# Grove_-_Collision_Sensor_v2_0.net
KiCad netlist of a schematic drawn in EAGLE
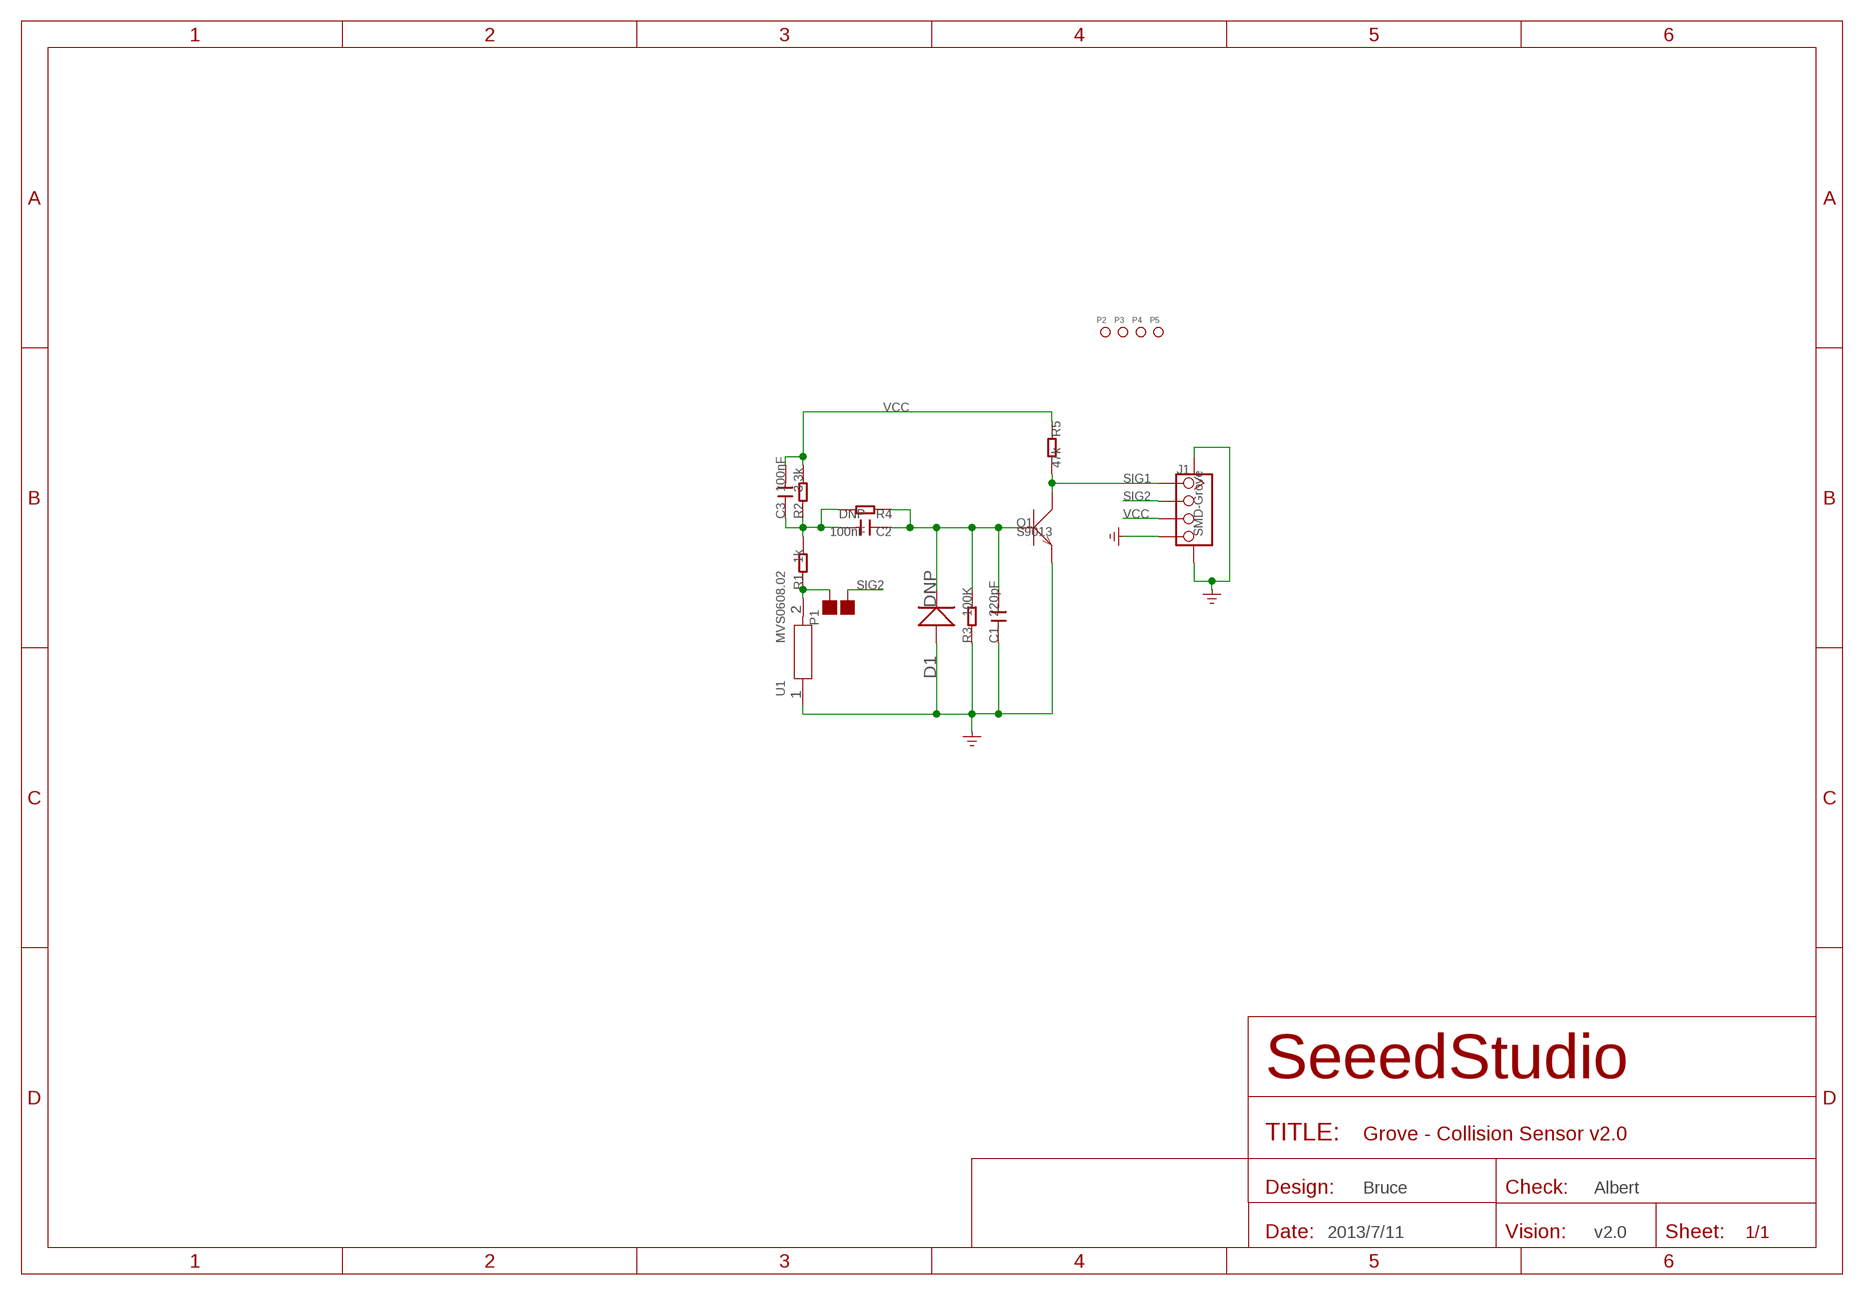
[diagram p0: schematic, sheet 1]

(export (version "E")
  (design (tool "Eeschema 10.0.6"))
  (components
    (comp (ref "C1")
      (value "220pF")
      (footprint "eagle-import:C0603")
      (libsource (lib "eagle-import") (part "C-0603"))
    )
    (comp (ref "C2")
      (value "100nF")
      (footprint "eagle-import:C0603")
      (libsource (lib "eagle-import") (part "C-0603"))
    )
    (comp (ref "C3")
      (value "100nF")
      (footprint "eagle-import:C0603")
      (libsource (lib "eagle-import") (part "C-0603"))
    )
    (comp (ref "D1")
      (value "DNP")
      (footprint "eagle-import:SOD123")
      (libsource (lib "eagle-import") (part "D'1206'"))
    )
    (comp (ref "J1")
      (value "SMD-Grove")
      (footprint "eagle-import:4P-SMD-2.0")
      (libsource (lib "eagle-import") (part "TWIG-4P-2.0-SMD-FEMALE-REINFORCE'DD'"))
    )
    (comp (ref "P1")
      (value "DNP")
      (footprint "eagle-import:2P-SMD-1.78X1.27")
      (libsource (lib "eagle-import") (part "PAD-JUMPER-2P"))
    )
    (comp (ref "P2")
      (value "PAD-MARK")
      (footprint "eagle-import:ROUND-MARK-1.0")
      (fields (field (name "PARTNO") "DNP"))
      (libsource (lib "eagle-import") (part "PAD-MARK"))
    )
    (comp (ref "P3")
      (value "PAD-MARK")
      (footprint "eagle-import:ROUND-MARK-1.0")
      (fields (field (name "PARTNO") "DNP"))
      (libsource (lib "eagle-import") (part "PAD-MARK"))
    )
    (comp (ref "P4")
      (value "PAD-MARK")
      (footprint "eagle-import:ROUND-MARK-1.0")
      (fields (field (name "PARTNO") "DNP"))
      (libsource (lib "eagle-import") (part "PAD-MARK"))
    )
    (comp (ref "P5")
      (value "PAD-MARK")
      (footprint "eagle-import:ROUND-MARK-1.0")
      (fields (field (name "PARTNO") "DNP"))
      (libsource (lib "eagle-import") (part "PAD-MARK"))
    )
    (comp (ref "Q1")
      (value "S9013")
      (footprint "eagle-import:SOT23")
      (libsource (lib "eagle-import") (part "TRANSISTOR-NPN-SOT23"))
    )
    (comp (ref "R1")
      (value "1k")
      (footprint "eagle-import:R0603")
      (libsource (lib "eagle-import") (part "R-0603"))
    )
    (comp (ref "R2")
      (value "3.3k")
      (footprint "eagle-import:R0603")
      (libsource (lib "eagle-import") (part "R-0603"))
    )
    (comp (ref "R3")
      (value "100K")
      (footprint "eagle-import:R0603")
      (libsource (lib "eagle-import") (part "R-0603"))
    )
    (comp (ref "R4")
      (value "DNP")
      (footprint "eagle-import:R0603")
      (libsource (lib "eagle-import") (part "R-0603"))
    )
    (comp (ref "R5")
      (value "47k")
      (footprint "eagle-import:R0603")
      (libsource (lib "eagle-import") (part "R-0603"))
    )
    (comp (ref "U1")
      (value "MVS0608.02")
      (footprint "eagle-import:2P-2.45X2.85X1.7H")
      (libsource (lib "eagle-import") (part "MVS0608.02"))
    )
  )
  (nets
    (net (code "1") (name "/SIG1") (class "Default")
      (node (ref "J1") (pin "1") (pinfunction "1_1") (pintype "bidirectional"))
      (node (ref "Q1") (pin "3") (pinfunction "C_3") (pintype "passive"))
      (node (ref "R5") (pin "2") (pinfunction "2_2") (pintype "passive"))
    )
    (net (code "2") (name "/SIG2") (class "Default")
      (node (ref "J1") (pin "2") (pinfunction "2_2") (pintype "bidirectional"))
      (node (ref "P1") (pin "1") (pinfunction "1_1") (pintype "bidirectional"))
    )
    (net (code "3") (name "/VCC") (class "Default")
      (node (ref "C3") (pin "2") (pinfunction "2_2") (pintype "passive"))
      (node (ref "J1") (pin "3") (pinfunction "3_3") (pintype "bidirectional"))
      (node (ref "R2") (pin "2") (pinfunction "2_2") (pintype "passive"))
      (node (ref "R5") (pin "1") (pinfunction "1_1") (pintype "passive"))
    )
    (net (code "4") (name "GND_POWER") (class "Default")
      (node (ref "C1") (pin "1") (pinfunction "1_1") (pintype "passive"))
      (node (ref "D1") (pin "+") (pinfunction "+_+") (pintype "passive"))
      (node (ref "J1") (pin "4") (pinfunction "4_4") (pintype "bidirectional"))
      (node (ref "J1") (pin "SS1") (pinfunction "SS1_SS1") (pintype "bidirectional"))
      (node (ref "J1") (pin "SS2") (pinfunction "SS2_SS2") (pintype "bidirectional"))
      (node (ref "Q1") (pin "2") (pinfunction "E_2") (pintype "passive"))
      (node (ref "R3") (pin "1") (pinfunction "1_1") (pintype "passive"))
      (node (ref "U1") (pin "1") (pinfunction "1_1") (pintype "bidirectional"))
    )
    (net (code "5") (name "Net-(C2-Pad2)") (class "Default")
      (node (ref "C2") (pin "2") (pinfunction "2_2") (pintype "passive"))
      (node (ref "C3") (pin "1") (pinfunction "1_1") (pintype "passive"))
      (node (ref "R1") (pin "2") (pinfunction "2_2") (pintype "passive"))
      (node (ref "R2") (pin "1") (pinfunction "1_1") (pintype "passive"))
      (node (ref "R4") (pin "2") (pinfunction "2_2") (pintype "passive"))
    )
    (net (code "6") (name "Net-(P1-Pad2)") (class "Default")
      (node (ref "P1") (pin "2") (pinfunction "2_2") (pintype "bidirectional"))
      (node (ref "R1") (pin "1") (pinfunction "1_1") (pintype "passive"))
      (node (ref "U1") (pin "2") (pinfunction "2_2") (pintype "bidirectional"))
    )
    (net (code "7") (name "Net-(Q1-B)") (class "Default")
      (node (ref "C1") (pin "2") (pinfunction "2_2") (pintype "passive"))
      (node (ref "C2") (pin "1") (pinfunction "1_1") (pintype "passive"))
      (node (ref "D1") (pin "-") (pinfunction "-_-") (pintype "passive"))
      (node (ref "Q1") (pin "1") (pinfunction "B_1") (pintype "passive"))
      (node (ref "R3") (pin "2") (pinfunction "2_2") (pintype "passive"))
      (node (ref "R4") (pin "1") (pinfunction "1_1") (pintype "passive"))
    )
  )
)
